# PCB-BI8-SE-E201.net
KiCad netlist of a schematic drawn in EAGLE
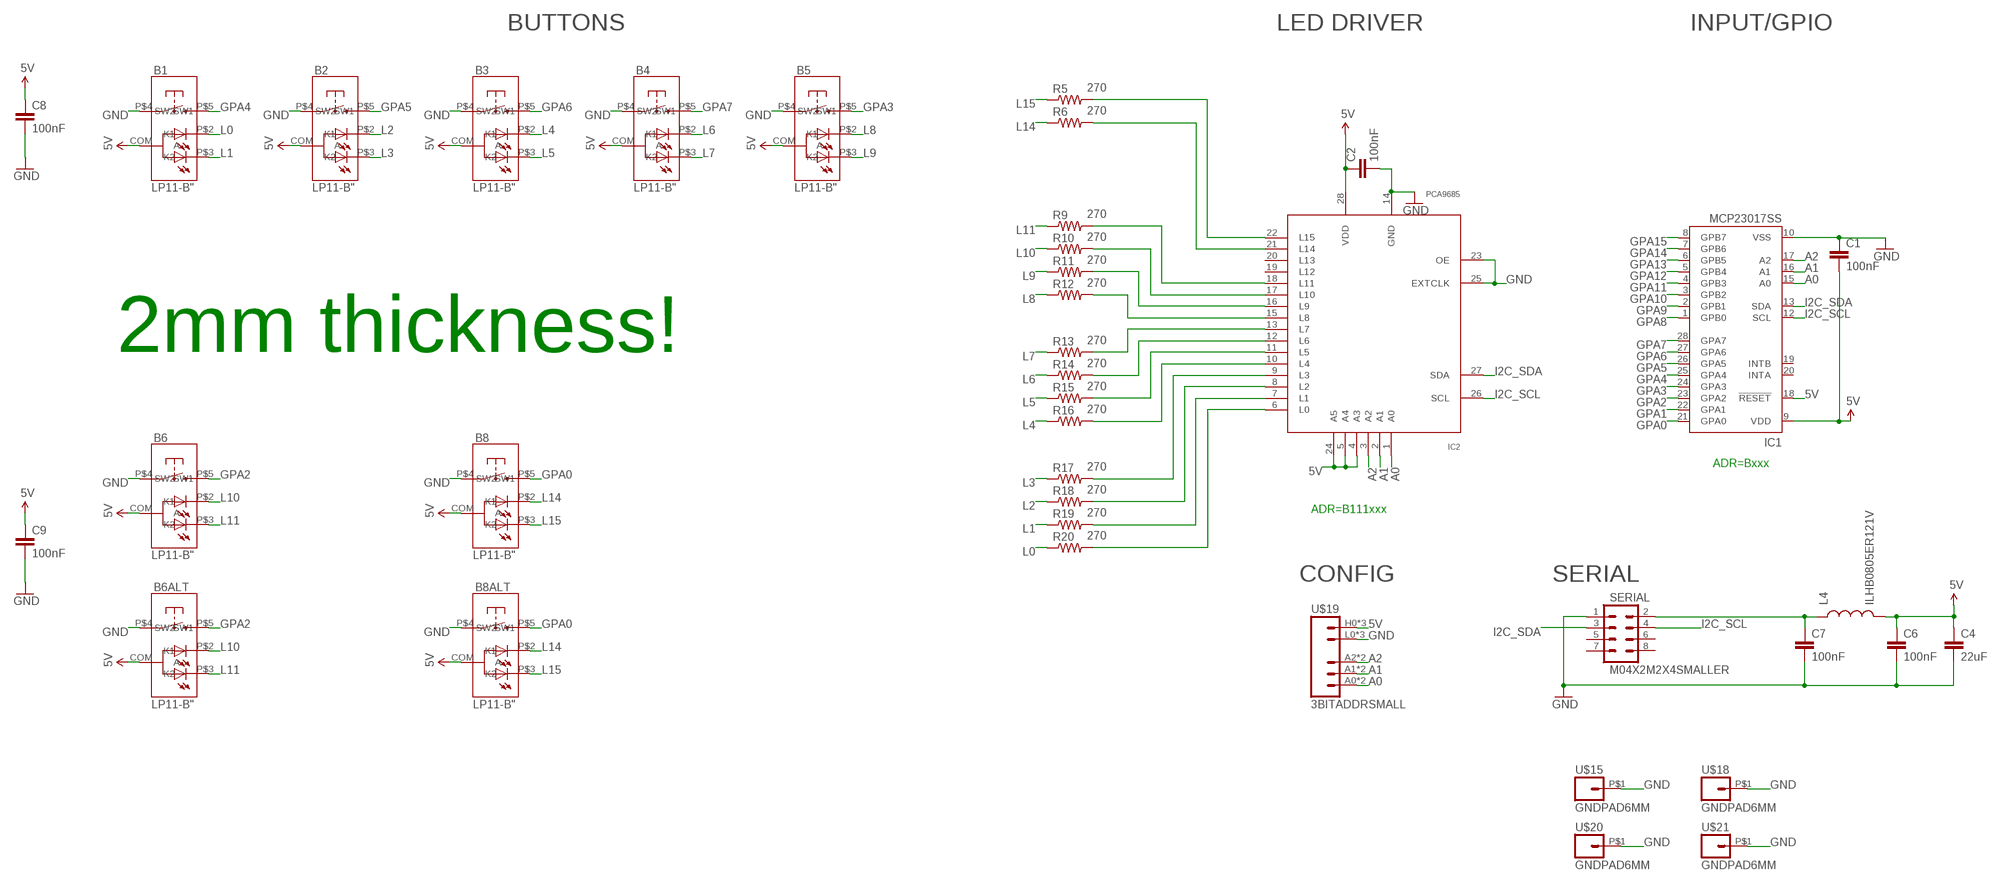
[diagram p0: schematic, sheet 1]

(export (version "E")
  (design (tool "Eeschema 10.0.6"))
  (components
    (comp (ref "B1")
      (value "LP11-B\"")
      (footprint "eagle-import:LP11")
      (libsource (lib "eagle-import") (part "LP11-B{dblquote}"))
    )
    (comp (ref "B2")
      (value "LP11-B\"")
      (footprint "eagle-import:LP11")
      (libsource (lib "eagle-import") (part "LP11-B{dblquote}"))
    )
    (comp (ref "B3")
      (value "LP11-B\"")
      (footprint "eagle-import:LP11")
      (libsource (lib "eagle-import") (part "LP11-B{dblquote}"))
    )
    (comp (ref "B4")
      (value "LP11-B\"")
      (footprint "eagle-import:LP11")
      (libsource (lib "eagle-import") (part "LP11-B{dblquote}"))
    )
    (comp (ref "B5")
      (value "LP11-B\"")
      (footprint "eagle-import:LP11")
      (libsource (lib "eagle-import") (part "LP11-B{dblquote}"))
    )
    (comp (ref "B6")
      (value "LP11-B\"")
      (footprint "eagle-import:LP11")
      (libsource (lib "eagle-import") (part "LP11-B{dblquote}"))
    )
    (comp (ref "B6ALT")
      (value "LP11-B\"")
      (footprint "eagle-import:LP11")
      (libsource (lib "eagle-import") (part "LP11-B{dblquote}"))
    )
    (comp (ref "B8")
      (value "LP11-B\"")
      (footprint "eagle-import:LP11")
      (libsource (lib "eagle-import") (part "LP11-B{dblquote}"))
    )
    (comp (ref "B8ALT")
      (value "LP11-B\"")
      (footprint "eagle-import:LP11")
      (libsource (lib "eagle-import") (part "LP11-B{dblquote}"))
    )
    (comp (ref "C1")
      (value "100nF")
      (footprint "eagle-import:0603-CAP")
      (libsource (lib "eagle-import") (part "CAP0603-CAP"))
    )
    (comp (ref "C2")
      (value "100nF")
      (footprint "eagle-import:0603-CAP")
      (libsource (lib "eagle-import") (part "CAP0603-CAP"))
    )
    (comp (ref "C4")
      (value "22uF")
      (footprint "eagle-import:0805")
      (libsource (lib "eagle-import") (part "CAP0805"))
    )
    (comp (ref "C6")
      (value "100nF")
      (footprint "eagle-import:0603-CAP")
      (libsource (lib "eagle-import") (part "CAP0603-CAP"))
    )
    (comp (ref "C7")
      (value "100nF")
      (footprint "eagle-import:0603-CAP")
      (libsource (lib "eagle-import") (part "CAP0603-CAP"))
    )
    (comp (ref "C8")
      (value "100nF")
      (footprint "eagle-import:0603-CAP")
      (libsource (lib "eagle-import") (part "CAP0603-CAP"))
    )
    (comp (ref "C9")
      (value "100nF")
      (footprint "eagle-import:0603-CAP")
      (libsource (lib "eagle-import") (part "CAP0603-CAP"))
    )
    (comp (ref "IC1")
      (value "MCP23017SS")
      (footprint "eagle-import:SSOP28")
      (fields
        (field (name "MF") "MICROCHIP")
        (field (name "MPN") "MCP23017-E/SS")
        (field (name "MPN_1") "MCP23017-E/SS")
        (field (name "OC_FARNELL") "1467674")
        (field (name "OC_NEWARK") "31K2960")
      )
      (libsource (lib "eagle-import") (part "MCP23017SS"))
    )
    (comp (ref "IC2")
      (value "PCA9685")
      (footprint "eagle-import:TSSOP28")
      (libsource (lib "eagle-import") (part "PCA9685"))
    )
    (comp (ref "L4")
      (value "ILHB0805ER121V")
      (footprint "eagle-import:0805")
      (libsource (lib "eagle-import") (part "INDUCTOR0805"))
    )
    (comp (ref "R5")
      (value "270")
      (footprint "eagle-import:0603-RES")
      (libsource (lib "eagle-import") (part "RESISTOR0603-RES"))
    )
    (comp (ref "R6")
      (value "270")
      (footprint "eagle-import:0603-RES")
      (libsource (lib "eagle-import") (part "RESISTOR0603-RES"))
    )
    (comp (ref "R9")
      (value "270")
      (footprint "eagle-import:0603-RES")
      (libsource (lib "eagle-import") (part "RESISTOR0603-RES"))
    )
    (comp (ref "R10")
      (value "270")
      (footprint "eagle-import:0603-RES")
      (libsource (lib "eagle-import") (part "RESISTOR0603-RES"))
    )
    (comp (ref "R11")
      (value "270")
      (footprint "eagle-import:0603-RES")
      (libsource (lib "eagle-import") (part "RESISTOR0603-RES"))
    )
    (comp (ref "R12")
      (value "270")
      (footprint "eagle-import:0603-RES")
      (libsource (lib "eagle-import") (part "RESISTOR0603-RES"))
    )
    (comp (ref "R13")
      (value "270")
      (footprint "eagle-import:0603-RES")
      (libsource (lib "eagle-import") (part "RESISTOR0603-RES"))
    )
    (comp (ref "R14")
      (value "270")
      (footprint "eagle-import:0603-RES")
      (libsource (lib "eagle-import") (part "RESISTOR0603-RES"))
    )
    (comp (ref "R15")
      (value "270")
      (footprint "eagle-import:0603-RES")
      (libsource (lib "eagle-import") (part "RESISTOR0603-RES"))
    )
    (comp (ref "R16")
      (value "270")
      (footprint "eagle-import:0603-RES")
      (libsource (lib "eagle-import") (part "RESISTOR0603-RES"))
    )
    (comp (ref "R17")
      (value "270")
      (footprint "eagle-import:0603-RES")
      (libsource (lib "eagle-import") (part "RESISTOR0603-RES"))
    )
    (comp (ref "R18")
      (value "270")
      (footprint "eagle-import:0603-RES")
      (libsource (lib "eagle-import") (part "RESISTOR0603-RES"))
    )
    (comp (ref "R19")
      (value "270")
      (footprint "eagle-import:0603-RES")
      (libsource (lib "eagle-import") (part "RESISTOR0603-RES"))
    )
    (comp (ref "R20")
      (value "270")
      (footprint "eagle-import:0603-RES")
      (libsource (lib "eagle-import") (part "RESISTOR0603-RES"))
    )
    (comp (ref "SERIAL")
      (value "M04X2M2X4SMALLER")
      (footprint "eagle-import:M2X4SMALLER")
      (libsource (lib "eagle-import") (part "M04X2M2X4SMALLER"))
    )
    (comp (ref "U$15")
      (value "GNDPAD6MM")
      (footprint "eagle-import:3.2MMPAD6MM")
      (libsource (lib "eagle-import") (part "GNDPAD6MM"))
    )
    (comp (ref "U$18")
      (value "GNDPAD6MM")
      (footprint "eagle-import:3.2MMPAD6MM")
      (libsource (lib "eagle-import") (part "GNDPAD6MM"))
    )
    (comp (ref "U$19")
      (value "3BITADDRSMALL")
      (footprint "eagle-import:3BITADDR_SMALL")
      (libsource (lib "eagle-import") (part "3BITADDRSMALL"))
    )
    (comp (ref "U$20")
      (value "GNDPAD6MM")
      (footprint "eagle-import:3.2MMPAD6MM")
      (libsource (lib "eagle-import") (part "GNDPAD6MM"))
    )
    (comp (ref "U$21")
      (value "GNDPAD6MM")
      (footprint "eagle-import:3.2MMPAD6MM")
      (libsource (lib "eagle-import") (part "GNDPAD6MM"))
    )
  )
  (nets
    (net (code "1") (name "5V") (class "Default")
      (node (ref "B1") (pin "COM") (pinfunction "A_COM") (pintype "bidirectional"))
      (node (ref "B2") (pin "COM") (pinfunction "A_COM") (pintype "bidirectional"))
      (node (ref "B3") (pin "COM") (pinfunction "A_COM") (pintype "bidirectional"))
      (node (ref "B4") (pin "COM") (pinfunction "A_COM") (pintype "bidirectional"))
      (node (ref "B5") (pin "COM") (pinfunction "A_COM") (pintype "bidirectional"))
      (node (ref "B6") (pin "COM") (pinfunction "A_COM") (pintype "bidirectional"))
      (node (ref "B6ALT") (pin "COM") (pinfunction "A_COM") (pintype "bidirectional"))
      (node (ref "B8") (pin "COM") (pinfunction "A_COM") (pintype "bidirectional"))
      (node (ref "B8ALT") (pin "COM") (pinfunction "A_COM") (pintype "bidirectional"))
      (node (ref "C1") (pin "2") (pinfunction "2_2") (pintype "passive"))
      (node (ref "C2") (pin "1") (pinfunction "1_1") (pintype "passive"))
      (node (ref "C4") (pin "1") (pinfunction "1_1") (pintype "passive"))
      (node (ref "C6") (pin "1") (pinfunction "1_1") (pintype "passive"))
      (node (ref "C8") (pin "1") (pinfunction "1_1") (pintype "passive"))
      (node (ref "C9") (pin "1") (pinfunction "1_1") (pintype "passive"))
      (node (ref "IC1") (pin "18") (pinfunction "~{RESET}_18") (pintype "input"))
      (node (ref "IC1") (pin "9") (pinfunction "VDD_9") (pintype "power_in"))
      (node (ref "IC2") (pin "24") (pinfunction "A5_24") (pintype "input"))
      (node (ref "IC2") (pin "28") (pinfunction "VDD_28") (pintype "power_in"))
      (node (ref "IC2") (pin "4") (pinfunction "A3_4") (pintype "input"))
      (node (ref "IC2") (pin "5") (pinfunction "A4_5") (pintype "input"))
      (node (ref "L4") (pin "2") (pinfunction "2_2") (pintype "passive"))
      (node (ref "U$19") (pin "H0") (pinfunction "VCC_H0") (pintype "passive"))
      (node (ref "U$19") (pin "H1") (pinfunction "VCC_H1") (pintype "passive"))
      (node (ref "U$19") (pin "H2") (pinfunction "VCC_H2") (pintype "passive"))
    )
    (net (code "2") (name "A0") (class "Default")
      (node (ref "IC1") (pin "15") (pinfunction "A0_15") (pintype "input"))
      (node (ref "IC2") (pin "1") (pinfunction "A0_1") (pintype "input"))
      (node (ref "U$19") (pin "A0") (pinfunction "A0_A0") (pintype "passive"))
      (node (ref "U$19") (pin "AS0") (pinfunction "A0_AS0") (pintype "passive"))
    )
    (net (code "3") (name "A1") (class "Default")
      (node (ref "IC1") (pin "16") (pinfunction "A1_16") (pintype "input"))
      (node (ref "IC2") (pin "2") (pinfunction "A1_2") (pintype "input"))
      (node (ref "U$19") (pin "A1") (pinfunction "A1_A1") (pintype "passive"))
      (node (ref "U$19") (pin "AS1") (pinfunction "A1_AS1") (pintype "passive"))
    )
    (net (code "4") (name "A2") (class "Default")
      (node (ref "IC1") (pin "17") (pinfunction "A2_17") (pintype "input"))
      (node (ref "IC2") (pin "3") (pinfunction "A2_3") (pintype "input"))
      (node (ref "U$19") (pin "A2") (pinfunction "A2_A2") (pintype "passive"))
      (node (ref "U$19") (pin "AS2") (pinfunction "A2_AS2") (pintype "passive"))
    )
    (net (code "5") (name "GND") (class "Default")
      (node (ref "B1") (pin "P$4") (pinfunction "SW1_P$4") (pintype "bidirectional"))
      (node (ref "B2") (pin "P$4") (pinfunction "SW1_P$4") (pintype "bidirectional"))
      (node (ref "B3") (pin "P$4") (pinfunction "SW1_P$4") (pintype "bidirectional"))
      (node (ref "B4") (pin "P$4") (pinfunction "SW1_P$4") (pintype "bidirectional"))
      (node (ref "B5") (pin "P$4") (pinfunction "SW1_P$4") (pintype "bidirectional"))
      (node (ref "B6") (pin "P$4") (pinfunction "SW1_P$4") (pintype "bidirectional"))
      (node (ref "B6ALT") (pin "P$4") (pinfunction "SW1_P$4") (pintype "bidirectional"))
      (node (ref "B8") (pin "P$4") (pinfunction "SW1_P$4") (pintype "bidirectional"))
      (node (ref "B8ALT") (pin "P$4") (pinfunction "SW1_P$4") (pintype "bidirectional"))
      (node (ref "C1") (pin "1") (pinfunction "1_1") (pintype "passive"))
      (node (ref "C2") (pin "2") (pinfunction "2_2") (pintype "passive"))
      (node (ref "C4") (pin "2") (pinfunction "2_2") (pintype "passive"))
      (node (ref "C6") (pin "2") (pinfunction "2_2") (pintype "passive"))
      (node (ref "C7") (pin "2") (pinfunction "2_2") (pintype "passive"))
      (node (ref "C8") (pin "2") (pinfunction "2_2") (pintype "passive"))
      (node (ref "C9") (pin "2") (pinfunction "2_2") (pintype "passive"))
      (node (ref "IC1") (pin "10") (pinfunction "VSS_10") (pintype "power_in"))
      (node (ref "IC2") (pin "14") (pinfunction "GND_14") (pintype "power_in"))
      (node (ref "IC2") (pin "23") (pinfunction "OE_23") (pintype "input"))
      (node (ref "IC2") (pin "25") (pinfunction "EXTCLK_25") (pintype "input"))
      (node (ref "SERIAL") (pin "1") (pinfunction "1_1") (pintype "passive"))
      (node (ref "U$15") (pin "P$1") (pinfunction "1_P$1") (pintype "passive"))
      (node (ref "U$18") (pin "P$1") (pinfunction "1_P$1") (pintype "passive"))
      (node (ref "U$19") (pin "L0") (pinfunction "GND_L0") (pintype "passive"))
      (node (ref "U$19") (pin "L1") (pinfunction "GND_L1") (pintype "passive"))
      (node (ref "U$19") (pin "L2") (pinfunction "GND_L2") (pintype "passive"))
      (node (ref "U$20") (pin "P$1") (pinfunction "1_P$1") (pintype "passive"))
      (node (ref "U$21") (pin "P$1") (pinfunction "1_P$1") (pintype "passive"))
    )
    (net (code "6") (name "GPA0") (class "Default")
      (node (ref "B8") (pin "P$5") (pinfunction "SW2_P$5") (pintype "bidirectional"))
      (node (ref "B8ALT") (pin "P$5") (pinfunction "SW2_P$5") (pintype "bidirectional"))
      (node (ref "IC1") (pin "21") (pinfunction "GPA0_21") (pintype "bidirectional"))
    )
    (net (code "7") (name "GPA1") (class "Default")
      (node (ref "IC1") (pin "22") (pinfunction "GPA1_22") (pintype "bidirectional"))
    )
    (net (code "8") (name "GPA2") (class "Default")
      (node (ref "B6") (pin "P$5") (pinfunction "SW2_P$5") (pintype "bidirectional"))
      (node (ref "B6ALT") (pin "P$5") (pinfunction "SW2_P$5") (pintype "bidirectional"))
      (node (ref "IC1") (pin "23") (pinfunction "GPA2_23") (pintype "bidirectional"))
    )
    (net (code "9") (name "GPA3") (class "Default")
      (node (ref "B5") (pin "P$5") (pinfunction "SW2_P$5") (pintype "bidirectional"))
      (node (ref "IC1") (pin "24") (pinfunction "GPA3_24") (pintype "bidirectional"))
    )
    (net (code "10") (name "GPA4") (class "Default")
      (node (ref "B1") (pin "P$5") (pinfunction "SW2_P$5") (pintype "bidirectional"))
      (node (ref "IC1") (pin "25") (pinfunction "GPA4_25") (pintype "bidirectional"))
    )
    (net (code "11") (name "GPA5") (class "Default")
      (node (ref "B2") (pin "P$5") (pinfunction "SW2_P$5") (pintype "bidirectional"))
      (node (ref "IC1") (pin "26") (pinfunction "GPA5_26") (pintype "bidirectional"))
    )
    (net (code "12") (name "GPA6") (class "Default")
      (node (ref "B3") (pin "P$5") (pinfunction "SW2_P$5") (pintype "bidirectional"))
      (node (ref "IC1") (pin "27") (pinfunction "GPA6_27") (pintype "bidirectional"))
    )
    (net (code "13") (name "GPA7") (class "Default")
      (node (ref "B4") (pin "P$5") (pinfunction "SW2_P$5") (pintype "bidirectional"))
      (node (ref "IC1") (pin "28") (pinfunction "GPA7_28") (pintype "bidirectional"))
    )
    (net (code "14") (name "GPA8") (class "Default")
      (node (ref "IC1") (pin "1") (pinfunction "GPB0_1") (pintype "bidirectional"))
    )
    (net (code "15") (name "GPA9") (class "Default")
      (node (ref "IC1") (pin "2") (pinfunction "GPB1_2") (pintype "bidirectional"))
    )
    (net (code "16") (name "GPA10") (class "Default")
      (node (ref "IC1") (pin "3") (pinfunction "GPB2_3") (pintype "bidirectional"))
    )
    (net (code "17") (name "GPA11") (class "Default")
      (node (ref "IC1") (pin "4") (pinfunction "GPB3_4") (pintype "bidirectional"))
    )
    (net (code "18") (name "GPA12") (class "Default")
      (node (ref "IC1") (pin "5") (pinfunction "GPB4_5") (pintype "bidirectional"))
    )
    (net (code "19") (name "GPA13") (class "Default")
      (node (ref "IC1") (pin "6") (pinfunction "GPB5_6") (pintype "bidirectional"))
    )
    (net (code "20") (name "GPA14") (class "Default")
      (node (ref "IC1") (pin "7") (pinfunction "GPB6_7") (pintype "bidirectional"))
    )
    (net (code "21") (name "GPA15") (class "Default")
      (node (ref "IC1") (pin "8") (pinfunction "GPB7_8") (pintype "bidirectional"))
    )
    (net (code "22") (name "I2C_SCL") (class "Default")
      (node (ref "IC1") (pin "12") (pinfunction "SCL_12") (pintype "input"))
      (node (ref "IC2") (pin "26") (pinfunction "SCL_26") (pintype "input"))
      (node (ref "SERIAL") (pin "4") (pinfunction "4_4") (pintype "passive"))
    )
    (net (code "23") (name "I2C_SDA") (class "Default")
      (node (ref "IC1") (pin "13") (pinfunction "SDA_13") (pintype "bidirectional"))
      (node (ref "IC2") (pin "27") (pinfunction "SDA_27") (pintype "input"))
      (node (ref "SERIAL") (pin "3") (pinfunction "3_3") (pintype "passive"))
    )
    (net (code "24") (name "L0") (class "Default")
      (node (ref "B1") (pin "P$2") (pinfunction "K1_P$2") (pintype "bidirectional"))
      (node (ref "R20") (pin "1") (pinfunction "1_1") (pintype "passive"))
    )
    (net (code "25") (name "L1") (class "Default")
      (node (ref "B1") (pin "P$3") (pinfunction "K2_P$3") (pintype "bidirectional"))
      (node (ref "R19") (pin "1") (pinfunction "1_1") (pintype "passive"))
    )
    (net (code "26") (name "L2") (class "Default")
      (node (ref "B2") (pin "P$2") (pinfunction "K1_P$2") (pintype "bidirectional"))
      (node (ref "R18") (pin "1") (pinfunction "1_1") (pintype "passive"))
    )
    (net (code "27") (name "L3") (class "Default")
      (node (ref "B2") (pin "P$3") (pinfunction "K2_P$3") (pintype "bidirectional"))
      (node (ref "R17") (pin "1") (pinfunction "1_1") (pintype "passive"))
    )
    (net (code "28") (name "L4") (class "Default")
      (node (ref "B3") (pin "P$2") (pinfunction "K1_P$2") (pintype "bidirectional"))
      (node (ref "R16") (pin "1") (pinfunction "1_1") (pintype "passive"))
    )
    (net (code "29") (name "L5") (class "Default")
      (node (ref "B3") (pin "P$3") (pinfunction "K2_P$3") (pintype "bidirectional"))
      (node (ref "R15") (pin "1") (pinfunction "1_1") (pintype "passive"))
    )
    (net (code "30") (name "L6") (class "Default")
      (node (ref "B4") (pin "P$2") (pinfunction "K1_P$2") (pintype "bidirectional"))
      (node (ref "R14") (pin "1") (pinfunction "1_1") (pintype "passive"))
    )
    (net (code "31") (name "L7") (class "Default")
      (node (ref "B4") (pin "P$3") (pinfunction "K2_P$3") (pintype "bidirectional"))
      (node (ref "R13") (pin "1") (pinfunction "1_1") (pintype "passive"))
    )
    (net (code "32") (name "L8") (class "Default")
      (node (ref "B5") (pin "P$2") (pinfunction "K1_P$2") (pintype "bidirectional"))
      (node (ref "R12") (pin "1") (pinfunction "1_1") (pintype "passive"))
    )
    (net (code "33") (name "L9") (class "Default")
      (node (ref "B5") (pin "P$3") (pinfunction "K2_P$3") (pintype "bidirectional"))
      (node (ref "R11") (pin "1") (pinfunction "1_1") (pintype "passive"))
    )
    (net (code "34") (name "L10") (class "Default")
      (node (ref "B6") (pin "P$2") (pinfunction "K1_P$2") (pintype "bidirectional"))
      (node (ref "B6ALT") (pin "P$2") (pinfunction "K1_P$2") (pintype "bidirectional"))
      (node (ref "R10") (pin "1") (pinfunction "1_1") (pintype "passive"))
    )
    (net (code "35") (name "L11") (class "Default")
      (node (ref "B6") (pin "P$3") (pinfunction "K2_P$3") (pintype "bidirectional"))
      (node (ref "B6ALT") (pin "P$3") (pinfunction "K2_P$3") (pintype "bidirectional"))
      (node (ref "R9") (pin "1") (pinfunction "1_1") (pintype "passive"))
    )
    (net (code "36") (name "L14") (class "Default")
      (node (ref "B8") (pin "P$2") (pinfunction "K1_P$2") (pintype "bidirectional"))
      (node (ref "B8ALT") (pin "P$2") (pinfunction "K1_P$2") (pintype "bidirectional"))
      (node (ref "R6") (pin "1") (pinfunction "1_1") (pintype "passive"))
    )
    (net (code "37") (name "L15") (class "Default")
      (node (ref "B8") (pin "P$3") (pinfunction "K2_P$3") (pintype "bidirectional"))
      (node (ref "B8ALT") (pin "P$3") (pinfunction "K2_P$3") (pintype "bidirectional"))
      (node (ref "R5") (pin "1") (pinfunction "1_1") (pintype "passive"))
    )
    (net (code "38") (name "Net-(C7-Pad1)") (class "Default")
      (node (ref "C7") (pin "1") (pinfunction "1_1") (pintype "passive"))
      (node (ref "L4") (pin "1") (pinfunction "1_1") (pintype "passive"))
      (node (ref "SERIAL") (pin "2") (pinfunction "2_2") (pintype "passive"))
    )
    (net (code "39") (name "Net-(IC2-L0)") (class "Default")
      (node (ref "IC2") (pin "6") (pinfunction "L0_6") (pintype "output"))
      (node (ref "R20") (pin "2") (pinfunction "2_2") (pintype "passive"))
    )
    (net (code "40") (name "Net-(IC2-L1)") (class "Default")
      (node (ref "IC2") (pin "7") (pinfunction "L1_7") (pintype "output"))
      (node (ref "R19") (pin "2") (pinfunction "2_2") (pintype "passive"))
    )
    (net (code "41") (name "Net-(IC2-L2)") (class "Default")
      (node (ref "IC2") (pin "8") (pinfunction "L2_8") (pintype "output"))
      (node (ref "R18") (pin "2") (pinfunction "2_2") (pintype "passive"))
    )
    (net (code "42") (name "Net-(IC2-L3)") (class "Default")
      (node (ref "IC2") (pin "9") (pinfunction "L3_9") (pintype "output"))
      (node (ref "R17") (pin "2") (pinfunction "2_2") (pintype "passive"))
    )
    (net (code "43") (name "Net-(IC2-L4)") (class "Default")
      (node (ref "IC2") (pin "10") (pinfunction "L4_10") (pintype "output"))
      (node (ref "R16") (pin "2") (pinfunction "2_2") (pintype "passive"))
    )
    (net (code "44") (name "Net-(IC2-L5)") (class "Default")
      (node (ref "IC2") (pin "11") (pinfunction "L5_11") (pintype "output"))
      (node (ref "R15") (pin "2") (pinfunction "2_2") (pintype "passive"))
    )
    (net (code "45") (name "Net-(IC2-L6)") (class "Default")
      (node (ref "IC2") (pin "12") (pinfunction "L6_12") (pintype "output"))
      (node (ref "R14") (pin "2") (pinfunction "2_2") (pintype "passive"))
    )
    (net (code "46") (name "Net-(IC2-L7)") (class "Default")
      (node (ref "IC2") (pin "13") (pinfunction "L7_13") (pintype "output"))
      (node (ref "R13") (pin "2") (pinfunction "2_2") (pintype "passive"))
    )
    (net (code "47") (name "Net-(IC2-L8)") (class "Default")
      (node (ref "IC2") (pin "15") (pinfunction "L8_15") (pintype "output"))
      (node (ref "R12") (pin "2") (pinfunction "2_2") (pintype "passive"))
    )
    (net (code "48") (name "Net-(IC2-L9)") (class "Default")
      (node (ref "IC2") (pin "16") (pinfunction "L9_16") (pintype "output"))
      (node (ref "R11") (pin "2") (pinfunction "2_2") (pintype "passive"))
    )
    (net (code "49") (name "Net-(IC2-L10)") (class "Default")
      (node (ref "IC2") (pin "17") (pinfunction "L10_17") (pintype "output"))
      (node (ref "R10") (pin "2") (pinfunction "2_2") (pintype "passive"))
    )
    (net (code "50") (name "Net-(IC2-L11)") (class "Default")
      (node (ref "IC2") (pin "18") (pinfunction "L11_18") (pintype "output"))
      (node (ref "R9") (pin "2") (pinfunction "2_2") (pintype "passive"))
    )
    (net (code "51") (name "Net-(IC2-L14)") (class "Default")
      (node (ref "IC2") (pin "21") (pinfunction "L14_21") (pintype "output"))
      (node (ref "R6") (pin "2") (pinfunction "2_2") (pintype "passive"))
    )
    (net (code "52") (name "Net-(IC2-L15)") (class "Default")
      (node (ref "IC2") (pin "22") (pinfunction "L15_22") (pintype "output"))
      (node (ref "R5") (pin "2") (pinfunction "2_2") (pintype "passive"))
    )
    (net (code "53") (name "unconnected-(IC1-INTA-Pad20)") (class "Default")
      (node (ref "IC1") (pin "20") (pinfunction "INTA_20") (pintype "output"))
    )
    (net (code "54") (name "unconnected-(IC1-INTB-Pad19)") (class "Default")
      (node (ref "IC1") (pin "19") (pinfunction "INTB_19") (pintype "output"))
    )
    (net (code "55") (name "unconnected-(IC2-L12-Pad19)") (class "Default")
      (node (ref "IC2") (pin "19") (pinfunction "L12_19") (pintype "output"))
    )
    (net (code "56") (name "unconnected-(IC2-L13-Pad20)") (class "Default")
      (node (ref "IC2") (pin "20") (pinfunction "L13_20") (pintype "output"))
    )
    (net (code "57") (name "unconnected-(SERIAL-Pad5)") (class "Default")
      (node (ref "SERIAL") (pin "5") (pinfunction "5_5") (pintype "passive"))
    )
    (net (code "58") (name "unconnected-(SERIAL-Pad6)") (class "Default")
      (node (ref "SERIAL") (pin "6") (pinfunction "6_6") (pintype "passive"))
    )
    (net (code "59") (name "unconnected-(SERIAL-Pad7)") (class "Default")
      (node (ref "SERIAL") (pin "7") (pinfunction "7_7") (pintype "passive"))
    )
    (net (code "60") (name "unconnected-(SERIAL-Pad8)") (class "Default")
      (node (ref "SERIAL") (pin "8") (pinfunction "8_8") (pintype "passive"))
    )
  )
)
